# LED_bargraph.net
KiCad netlist of a schematic drawn in Altium Designer
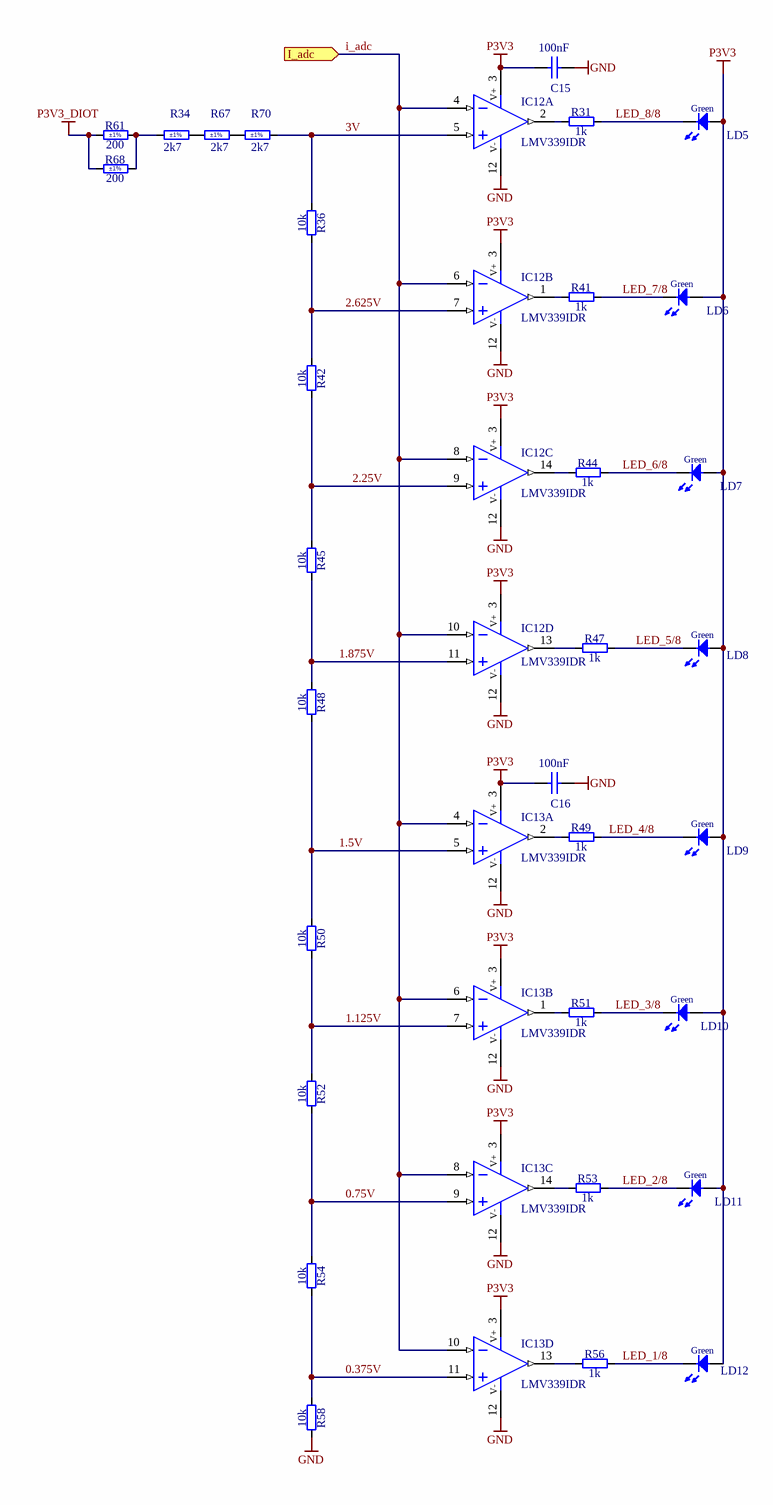
[diagram p0: LED_bargraph.SchDoc]

(export (version "E")
  (design (tool "Eeschema 10.0.6"))
  (components
    (comp (ref "C15")
      (value "100nF")
      (footprint "CAPC1005X55N")
      (description "Non-polarised capacitor")
      (fields
        (field (name "PART NUMBER") "CC0402_100NF_50V_10%_X7R")
        (field (name "VOLTAGE") "50V")
        (field (name "AUTHOR") "CERN DEM MR")
      )
      (libsource (lib "Capacitors") (part "Capacitor - non polarized"))
    )
    (comp (ref "C16")
      (value "100nF")
      (footprint "CAPC1005X55N")
      (description "Non-polarised capacitor")
      (fields
        (field (name "PART NUMBER") "CC0402_100NF_50V_10%_X7R")
        (field (name "VOLTAGE") "50V")
        (field (name "AUTHOR") "CERN DEM MR")
      )
      (libsource (lib "Capacitors") (part "Capacitor - non polarized"))
    )
    (comp (ref "IC12")
      (value "LMV339IDR")
      (footprint "SOIC127P600X175-14N")
      (description "Quad Differential Rail to Rail Comparator")
      (fields (field (name "MANUFACTURER") "TEXAS INSTRUMENTS") (field (name "AUTHOR") "GK"))
      (libsource (lib "Amplifiers") (part "CMP_LMV339"))
    )
    (comp (ref "IC13")
      (value "LMV339IDR")
      (footprint "SOIC127P600X175-14N")
      (description "Quad Differential Rail to Rail Comparator")
      (fields (field (name "MANUFACTURER") "TEXAS INSTRUMENTS") (field (name "AUTHOR") "GK"))
      (libsource (lib "Amplifiers") (part "CMP_LMV339"))
    )
    (comp (ref "LD5")
      (value "Green")
      (footprint "LED_AVAGO_HSME-C120")
      (description "LED Green 1C 2A")
      (fields
        (field (name "PART NUMBER") "LED_AVAGO_HSME-C120")
        (field (name "MANUFACTURER") "AVAGO TECHNOLOGIES")
        (field (name "AUTHOR") "CERN DEM JMW")
      )
      (libsource (lib "ICs And Semiconductors") (part "LED Green 1C 2A"))
    )
    (comp (ref "LD6")
      (value "Green")
      (footprint "LED_AVAGO_HSME-C120")
      (description "LED Green 1C 2A")
      (fields
        (field (name "PART NUMBER") "LED_AVAGO_HSME-C120")
        (field (name "MANUFACTURER") "AVAGO TECHNOLOGIES")
        (field (name "AUTHOR") "CERN DEM JMW")
      )
      (libsource (lib "ICs And Semiconductors") (part "LED Green 1C 2A"))
    )
    (comp (ref "LD7")
      (value "Green")
      (footprint "LED_AVAGO_HSME-C120")
      (description "LED Green 1C 2A")
      (fields
        (field (name "PART NUMBER") "LED_AVAGO_HSME-C120")
        (field (name "MANUFACTURER") "AVAGO TECHNOLOGIES")
        (field (name "AUTHOR") "CERN DEM JMW")
      )
      (libsource (lib "ICs And Semiconductors") (part "LED Green 1C 2A"))
    )
    (comp (ref "LD8")
      (value "Green")
      (footprint "LED_AVAGO_HSME-C120")
      (description "LED Green 1C 2A")
      (fields
        (field (name "PART NUMBER") "LED_AVAGO_HSME-C120")
        (field (name "MANUFACTURER") "AVAGO TECHNOLOGIES")
        (field (name "AUTHOR") "CERN DEM JMW")
      )
      (libsource (lib "ICs And Semiconductors") (part "LED Green 1C 2A"))
    )
    (comp (ref "LD9")
      (value "Green")
      (footprint "LED_AVAGO_HSME-C120")
      (description "LED Green 1C 2A")
      (fields
        (field (name "PART NUMBER") "LED_AVAGO_HSME-C120")
        (field (name "MANUFACTURER") "AVAGO TECHNOLOGIES")
        (field (name "AUTHOR") "CERN DEM JMW")
      )
      (libsource (lib "ICs And Semiconductors") (part "LED Green 1C 2A"))
    )
    (comp (ref "LD10")
      (value "Green")
      (footprint "LED_AVAGO_HSME-C120")
      (description "LED Green 1C 2A")
      (fields
        (field (name "PART NUMBER") "LED_AVAGO_HSME-C120")
        (field (name "MANUFACTURER") "AVAGO TECHNOLOGIES")
        (field (name "AUTHOR") "CERN DEM JMW")
      )
      (libsource (lib "ICs And Semiconductors") (part "LED Green 1C 2A"))
    )
    (comp (ref "LD11")
      (value "Green")
      (footprint "LED_AVAGO_HSME-C120")
      (description "LED Green 1C 2A")
      (fields
        (field (name "PART NUMBER") "LED_AVAGO_HSME-C120")
        (field (name "MANUFACTURER") "AVAGO TECHNOLOGIES")
        (field (name "AUTHOR") "CERN DEM JMW")
      )
      (libsource (lib "ICs And Semiconductors") (part "LED Green 1C 2A"))
    )
    (comp (ref "LD12")
      (value "Green")
      (footprint "LED_AVAGO_HSME-C120")
      (description "LED Green 1C 2A")
      (fields
        (field (name "PART NUMBER") "LED_AVAGO_HSME-C120")
        (field (name "MANUFACTURER") "AVAGO TECHNOLOGIES")
        (field (name "AUTHOR") "CERN DEM JMW")
      )
      (libsource (lib "ICs And Semiconductors") (part "LED Green 1C 2A"))
    )
    (comp (ref "R31")
      (value "1k")
      (footprint "RESC1608X55N")
      (description "Resistor - 1%")
      (fields
        (field (name "PART NUMBER") "R0603_1K_1%_0.1W_100PPM")
        (field (name "POWER") "0.1W")
        (field (name "AUTHOR") "CERN DEM JLC")
      )
      (libsource (lib "Resistors") (part "Resistor - 1%"))
    )
    (comp (ref "R34")
      (value "2k7")
      (footprint "RESC1608X55N")
      (description "Resistor - 1%")
      (fields
        (field (name "TOLERANCE") "±1%")
        (field (name "PART NUMBER") "R0603_2K7_1%_0.1W_100PPM")
        (field (name "POWER") "0.1W")
        (field (name "AUTHOR") "CERN DEM JLC")
      )
      (libsource (lib "Resistors") (part "Resistor - 1%"))
    )
    (comp (ref "R36")
      (value "10k")
      (footprint "RESC1005X40N")
      (description "Resistor - 1%")
      (fields
        (field (name "PART NUMBER") "R0402_10K_1%_0.0625W_100PPM")
        (field (name "POWER") "0.0625W")
        (field (name "AUTHOR") "CERN DEM JLC")
      )
      (libsource (lib "Resistors") (part "Resistor - 1%"))
    )
    (comp (ref "R41")
      (value "1k")
      (footprint "RESC1608X55N")
      (description "Resistor - 1%")
      (fields
        (field (name "PART NUMBER") "R0603_1K_1%_0.1W_100PPM")
        (field (name "POWER") "0.1W")
        (field (name "AUTHOR") "CERN DEM JLC")
      )
      (libsource (lib "Resistors") (part "Resistor - 1%"))
    )
    (comp (ref "R42")
      (value "10k")
      (footprint "RESC1005X40N")
      (description "Resistor - 1%")
      (fields
        (field (name "PART NUMBER") "R0402_10K_1%_0.0625W_100PPM")
        (field (name "POWER") "0.0625W")
        (field (name "AUTHOR") "CERN DEM JLC")
      )
      (libsource (lib "Resistors") (part "Resistor - 1%"))
    )
    (comp (ref "R44")
      (value "1k")
      (footprint "RESC1608X55N")
      (description "Resistor - 1%")
      (fields
        (field (name "PART NUMBER") "R0603_1K_1%_0.1W_100PPM")
        (field (name "POWER") "0.1W")
        (field (name "AUTHOR") "CERN DEM JLC")
      )
      (libsource (lib "Resistors") (part "Resistor - 1%"))
    )
    (comp (ref "R45")
      (value "10k")
      (footprint "RESC1005X40N")
      (description "Resistor - 1%")
      (fields
        (field (name "PART NUMBER") "R0402_10K_1%_0.0625W_100PPM")
        (field (name "POWER") "0.0625W")
        (field (name "AUTHOR") "CERN DEM JLC")
      )
      (libsource (lib "Resistors") (part "Resistor - 1%"))
    )
    (comp (ref "R47")
      (value "1k")
      (footprint "RESC1608X55N")
      (description "Resistor - 1%")
      (fields
        (field (name "PART NUMBER") "R0603_1K_1%_0.1W_100PPM")
        (field (name "POWER") "0.1W")
        (field (name "AUTHOR") "CERN DEM JLC")
      )
      (libsource (lib "Resistors") (part "Resistor - 1%"))
    )
    (comp (ref "R48")
      (value "10k")
      (footprint "RESC1005X40N")
      (description "Resistor - 1%")
      (fields
        (field (name "PART NUMBER") "R0402_10K_1%_0.0625W_100PPM")
        (field (name "POWER") "0.0625W")
        (field (name "AUTHOR") "CERN DEM JLC")
      )
      (libsource (lib "Resistors") (part "Resistor - 1%"))
    )
    (comp (ref "R49")
      (value "1k")
      (footprint "RESC1608X55N")
      (description "Resistor - 1%")
      (fields
        (field (name "PART NUMBER") "R0603_1K_1%_0.1W_100PPM")
        (field (name "POWER") "0.1W")
        (field (name "AUTHOR") "CERN DEM JLC")
      )
      (libsource (lib "Resistors") (part "Resistor - 1%"))
    )
    (comp (ref "R50")
      (value "10k")
      (footprint "RESC1005X40N")
      (description "Resistor - 1%")
      (fields
        (field (name "PART NUMBER") "R0402_10K_1%_0.0625W_100PPM")
        (field (name "POWER") "0.0625W")
        (field (name "AUTHOR") "CERN DEM JLC")
      )
      (libsource (lib "Resistors") (part "Resistor - 1%"))
    )
    (comp (ref "R51")
      (value "1k")
      (footprint "RESC1608X55N")
      (description "Resistor - 1%")
      (fields
        (field (name "PART NUMBER") "R0603_1K_1%_0.1W_100PPM")
        (field (name "POWER") "0.1W")
        (field (name "AUTHOR") "CERN DEM JLC")
      )
      (libsource (lib "Resistors") (part "Resistor - 1%"))
    )
    (comp (ref "R52")
      (value "10k")
      (footprint "RESC1005X40N")
      (description "Resistor - 1%")
      (fields
        (field (name "PART NUMBER") "R0402_10K_1%_0.0625W_100PPM")
        (field (name "POWER") "0.0625W")
        (field (name "AUTHOR") "CERN DEM JLC")
      )
      (libsource (lib "Resistors") (part "Resistor - 1%"))
    )
    (comp (ref "R53")
      (value "1k")
      (footprint "RESC1608X55N")
      (description "Resistor - 1%")
      (fields
        (field (name "PART NUMBER") "R0603_1K_1%_0.1W_100PPM")
        (field (name "POWER") "0.1W")
        (field (name "AUTHOR") "CERN DEM JLC")
      )
      (libsource (lib "Resistors") (part "Resistor - 1%"))
    )
    (comp (ref "R54")
      (value "10k")
      (footprint "RESC1005X40N")
      (description "Resistor - 1%")
      (fields
        (field (name "PART NUMBER") "R0402_10K_1%_0.0625W_100PPM")
        (field (name "POWER") "0.0625W")
        (field (name "AUTHOR") "CERN DEM JLC")
      )
      (libsource (lib "Resistors") (part "Resistor - 1%"))
    )
    (comp (ref "R56")
      (value "1k")
      (footprint "RESC1608X55N")
      (description "Resistor - 1%")
      (fields
        (field (name "PART NUMBER") "R0603_1K_1%_0.1W_100PPM")
        (field (name "POWER") "0.1W")
        (field (name "AUTHOR") "CERN DEM JLC")
      )
      (libsource (lib "Resistors") (part "Resistor - 1%"))
    )
    (comp (ref "R58")
      (value "10k")
      (footprint "RESC1005X40N")
      (description "Resistor - 1%")
      (fields
        (field (name "PART NUMBER") "R0402_10K_1%_0.0625W_100PPM")
        (field (name "POWER") "0.0625W")
        (field (name "AUTHOR") "CERN DEM JLC")
      )
      (libsource (lib "Resistors") (part "Resistor - 1%"))
    )
    (comp (ref "R61")
      (value "200")
      (footprint "RESC1005X40N")
      (description "Resistor - 1%")
      (fields
        (field (name "TOLERANCE") "±1%")
        (field (name "PART NUMBER") "R0402_200R_1%_0.0625W_100PPM")
        (field (name "POWER") "0.0625W")
        (field (name "AUTHOR") "CERN DEM JLC")
      )
      (libsource (lib "Resistors") (part "Resistor - 1%"))
    )
    (comp (ref "R67")
      (value "2k7")
      (footprint "RESC1608X55N")
      (description "Resistor - 1%")
      (fields
        (field (name "TOLERANCE") "±1%")
        (field (name "PART NUMBER") "R0603_2K7_1%_0.1W_100PPM")
        (field (name "POWER") "0.1W")
        (field (name "AUTHOR") "CERN DEM JLC")
      )
      (libsource (lib "Resistors") (part "Resistor - 1%"))
    )
    (comp (ref "R68")
      (value "200")
      (footprint "RESC1005X40N")
      (description "Resistor - 1%")
      (fields
        (field (name "TOLERANCE") "±1%")
        (field (name "PART NUMBER") "R0402_200R_1%_0.0625W_100PPM")
        (field (name "POWER") "0.0625W")
        (field (name "AUTHOR") "CERN DEM JLC")
      )
      (libsource (lib "Resistors") (part "Resistor - 1%"))
    )
    (comp (ref "R70")
      (value "2k7")
      (footprint "RESC1608X55N")
      (description "Resistor - 1%")
      (fields
        (field (name "TOLERANCE") "±1%")
        (field (name "PART NUMBER") "R0603_2K7_1%_0.1W_100PPM")
        (field (name "POWER") "0.1W")
        (field (name "AUTHOR") "CERN DEM JLC")
      )
      (libsource (lib "Resistors") (part "Resistor - 1%"))
    )
  )
  (nets
    (net (code "1") (name "/0.75V") (class "Default")
      (node (ref "IC13") (pin "9") (pinfunction "IN+_9") (pintype "input"))
      (node (ref "R52") (pin "2") (pinfunction "2_2") (pintype "passive"))
      (node (ref "R54") (pin "1") (pinfunction "1_1") (pintype "passive"))
    )
    (net (code "2") (name "/0.375V") (class "Default")
      (node (ref "IC13") (pin "11") (pinfunction "IN+_11") (pintype "input"))
      (node (ref "R54") (pin "2") (pinfunction "2_2") (pintype "passive"))
      (node (ref "R58") (pin "1") (pinfunction "1_1") (pintype "passive"))
    )
    (net (code "3") (name "/1.5V") (class "Default")
      (node (ref "IC13") (pin "5") (pinfunction "IN+_5") (pintype "input"))
      (node (ref "R48") (pin "2") (pinfunction "2_2") (pintype "passive"))
      (node (ref "R50") (pin "1") (pinfunction "1_1") (pintype "passive"))
    )
    (net (code "4") (name "/1.125V") (class "Default")
      (node (ref "IC13") (pin "7") (pinfunction "IN+_7") (pintype "input"))
      (node (ref "R50") (pin "2") (pinfunction "2_2") (pintype "passive"))
      (node (ref "R52") (pin "1") (pinfunction "1_1") (pintype "passive"))
    )
    (net (code "5") (name "/1.875V") (class "Default")
      (node (ref "IC12") (pin "11") (pinfunction "IN+_11") (pintype "input"))
      (node (ref "R45") (pin "2") (pinfunction "2_2") (pintype "passive"))
      (node (ref "R48") (pin "1") (pinfunction "1_1") (pintype "passive"))
    )
    (net (code "6") (name "/2.25V") (class "Default")
      (node (ref "IC12") (pin "9") (pinfunction "IN+_9") (pintype "input"))
      (node (ref "R42") (pin "2") (pinfunction "2_2") (pintype "passive"))
      (node (ref "R45") (pin "1") (pinfunction "1_1") (pintype "passive"))
    )
    (net (code "7") (name "/2.625V") (class "Default")
      (node (ref "IC12") (pin "7") (pinfunction "IN+_7") (pintype "input"))
      (node (ref "R36") (pin "2") (pinfunction "2_2") (pintype "passive"))
      (node (ref "R42") (pin "1") (pinfunction "1_1") (pintype "passive"))
    )
    (net (code "8") (name "/3V") (class "Default")
      (node (ref "IC12") (pin "5") (pinfunction "IN+_5") (pintype "input"))
      (node (ref "R36") (pin "1") (pinfunction "1_1") (pintype "passive"))
      (node (ref "R70") (pin "2") (pinfunction "2_2") (pintype "passive"))
    )
    (net (code "9") (name "/LED_1{slash}8") (class "Default")
      (node (ref "LD12") (pin "1") (pinfunction "C_1") (pintype "passive"))
      (node (ref "R56") (pin "2") (pinfunction "2_2") (pintype "passive"))
    )
    (net (code "10") (name "/LED_2{slash}8") (class "Default")
      (node (ref "LD11") (pin "1") (pinfunction "C_1") (pintype "passive"))
      (node (ref "R53") (pin "2") (pinfunction "2_2") (pintype "passive"))
    )
    (net (code "11") (name "/LED_3{slash}8") (class "Default")
      (node (ref "LD10") (pin "1") (pinfunction "C_1") (pintype "passive"))
      (node (ref "R51") (pin "2") (pinfunction "2_2") (pintype "passive"))
    )
    (net (code "12") (name "/LED_4{slash}8") (class "Default")
      (node (ref "LD9") (pin "1") (pinfunction "C_1") (pintype "passive"))
      (node (ref "R49") (pin "2") (pinfunction "2_2") (pintype "passive"))
    )
    (net (code "13") (name "/LED_5{slash}8") (class "Default")
      (node (ref "LD8") (pin "1") (pinfunction "C_1") (pintype "passive"))
      (node (ref "R47") (pin "2") (pinfunction "2_2") (pintype "passive"))
    )
    (net (code "14") (name "/LED_6{slash}8") (class "Default")
      (node (ref "LD7") (pin "1") (pinfunction "C_1") (pintype "passive"))
      (node (ref "R44") (pin "2") (pinfunction "2_2") (pintype "passive"))
    )
    (net (code "15") (name "/LED_7{slash}8") (class "Default")
      (node (ref "LD6") (pin "1") (pinfunction "C_1") (pintype "passive"))
      (node (ref "R41") (pin "2") (pinfunction "2_2") (pintype "passive"))
    )
    (net (code "16") (name "/LED_8{slash}8") (class "Default")
      (node (ref "LD5") (pin "1") (pinfunction "C_1") (pintype "passive"))
      (node (ref "R31") (pin "2") (pinfunction "2_2") (pintype "passive"))
    )
    (net (code "17") (name "/i_adc") (class "Default")
      (node (ref "IC12") (pin "10") (pinfunction "IN-_10") (pintype "input"))
      (node (ref "IC12") (pin "4") (pinfunction "IN-_4") (pintype "input"))
      (node (ref "IC12") (pin "6") (pinfunction "IN-_6") (pintype "input"))
      (node (ref "IC12") (pin "8") (pinfunction "IN-_8") (pintype "input"))
      (node (ref "IC13") (pin "10") (pinfunction "IN-_10") (pintype "input"))
      (node (ref "IC13") (pin "4") (pinfunction "IN-_4") (pintype "input"))
      (node (ref "IC13") (pin "6") (pinfunction "IN-_6") (pintype "input"))
      (node (ref "IC13") (pin "8") (pinfunction "IN-_8") (pintype "input"))
    )
    (net (code "18") (name "GND") (class "Default")
      (node (ref "C15") (pin "1") (pinfunction "1_1") (pintype "passive"))
      (node (ref "C16") (pin "1") (pinfunction "1_1") (pintype "passive"))
      (node (ref "IC12") (pin "12") (pinfunction "V-_12") (pintype "power_in"))
      (node (ref "IC13") (pin "12") (pinfunction "V-_12") (pintype "power_in"))
      (node (ref "R58") (pin "2") (pinfunction "2_2") (pintype "passive"))
    )
    (net (code "19") (name "Net-(IC12A-OUT)") (class "Default")
      (node (ref "IC12") (pin "2") (pinfunction "OUT_2") (pintype "output"))
      (node (ref "R31") (pin "1") (pinfunction "1_1") (pintype "passive"))
    )
    (net (code "20") (name "Net-(IC12B-OUT)") (class "Default")
      (node (ref "IC12") (pin "1") (pinfunction "OUT_1") (pintype "output"))
      (node (ref "R41") (pin "1") (pinfunction "1_1") (pintype "passive"))
    )
    (net (code "21") (name "Net-(IC12C-OUT)") (class "Default")
      (node (ref "IC12") (pin "14") (pinfunction "OUT_14") (pintype "output"))
      (node (ref "R44") (pin "1") (pinfunction "1_1") (pintype "passive"))
    )
    (net (code "22") (name "Net-(IC12D-OUT)") (class "Default")
      (node (ref "IC12") (pin "13") (pinfunction "OUT_13") (pintype "output"))
      (node (ref "R47") (pin "1") (pinfunction "1_1") (pintype "passive"))
    )
    (net (code "23") (name "Net-(IC13A-OUT)") (class "Default")
      (node (ref "IC13") (pin "2") (pinfunction "OUT_2") (pintype "output"))
      (node (ref "R49") (pin "1") (pinfunction "1_1") (pintype "passive"))
    )
    (net (code "24") (name "Net-(IC13B-OUT)") (class "Default")
      (node (ref "IC13") (pin "1") (pinfunction "OUT_1") (pintype "output"))
      (node (ref "R51") (pin "1") (pinfunction "1_1") (pintype "passive"))
    )
    (net (code "25") (name "Net-(IC13C-OUT)") (class "Default")
      (node (ref "IC13") (pin "14") (pinfunction "OUT_14") (pintype "output"))
      (node (ref "R53") (pin "1") (pinfunction "1_1") (pintype "passive"))
    )
    (net (code "26") (name "Net-(IC13D-OUT)") (class "Default")
      (node (ref "IC13") (pin "13") (pinfunction "OUT_13") (pintype "output"))
      (node (ref "R56") (pin "1") (pinfunction "1_1") (pintype "passive"))
    )
    (net (code "27") (name "Net-(R34-Pad1)") (class "Default")
      (node (ref "R34") (pin "1") (pinfunction "1_1") (pintype "passive"))
      (node (ref "R61") (pin "2") (pinfunction "2_2") (pintype "passive"))
      (node (ref "R68") (pin "2") (pinfunction "2_2") (pintype "passive"))
    )
    (net (code "28") (name "Net-(R34-Pad2)") (class "Default")
      (node (ref "R34") (pin "2") (pinfunction "2_2") (pintype "passive"))
      (node (ref "R67") (pin "1") (pinfunction "1_1") (pintype "passive"))
    )
    (net (code "29") (name "Net-(R67-Pad2)") (class "Default")
      (node (ref "R67") (pin "2") (pinfunction "2_2") (pintype "passive"))
      (node (ref "R70") (pin "1") (pinfunction "1_1") (pintype "passive"))
    )
    (net (code "30") (name "P3V3") (class "Default")
      (node (ref "C15") (pin "2") (pinfunction "2_2") (pintype "passive"))
      (node (ref "C16") (pin "2") (pinfunction "2_2") (pintype "passive"))
      (node (ref "IC12") (pin "3") (pinfunction "V+_3") (pintype "power_in"))
      (node (ref "IC13") (pin "3") (pinfunction "V+_3") (pintype "power_in"))
      (node (ref "LD10") (pin "2") (pinfunction "A_2") (pintype "passive"))
      (node (ref "LD11") (pin "2") (pinfunction "A_2") (pintype "passive"))
      (node (ref "LD12") (pin "2") (pinfunction "A_2") (pintype "passive"))
      (node (ref "LD5") (pin "2") (pinfunction "A_2") (pintype "passive"))
      (node (ref "LD6") (pin "2") (pinfunction "A_2") (pintype "passive"))
      (node (ref "LD7") (pin "2") (pinfunction "A_2") (pintype "passive"))
      (node (ref "LD8") (pin "2") (pinfunction "A_2") (pintype "passive"))
      (node (ref "LD9") (pin "2") (pinfunction "A_2") (pintype "passive"))
    )
    (net (code "31") (name "P3V3_DIOT") (class "Default")
      (node (ref "R61") (pin "1") (pinfunction "1_1") (pintype "passive"))
      (node (ref "R68") (pin "1") (pinfunction "1_1") (pintype "passive"))
    )
  )
)
